# Sheet1.net
KiCad netlist of a schematic drawn in Altium Designer
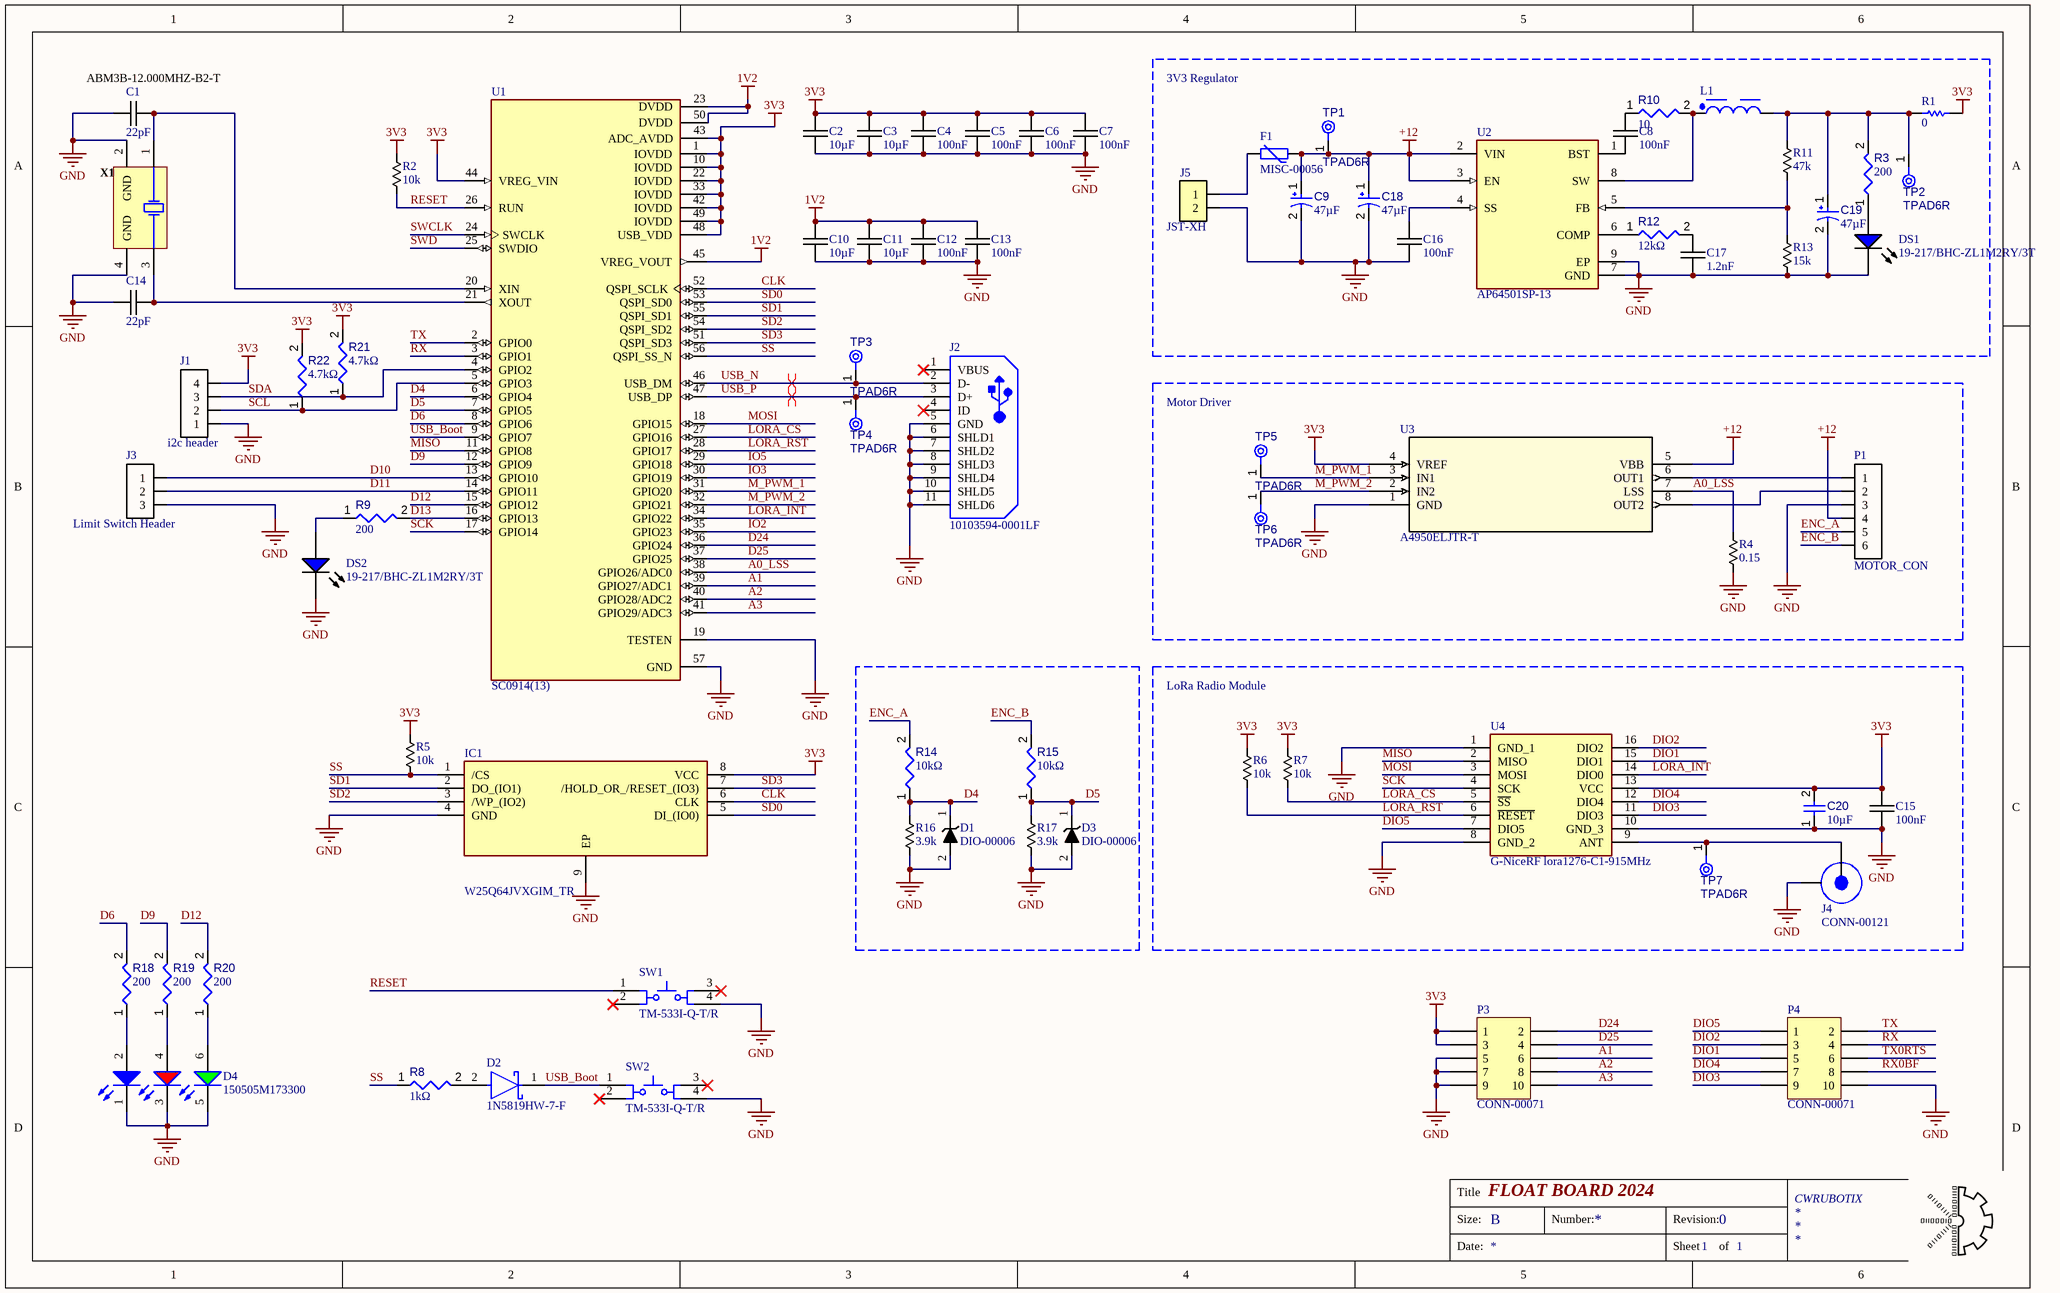
[diagram p0: Sheet1.SchDoc]

(export (version "E")
  (design (tool "Eeschema 10.0.6"))
  (components
    (comp (ref "C1")
      (value "22pF")
      (footprint "chip_0603")
      (description "CAP, 22pF, ±2%, 50V, C0G, 0603")
      (fields (field (name "MANUFACTURER") "Murata") (field (name "TOLERANCE") "2%"))
      (libsource (lib "Case Western Reserve University - Robotics Team") (part "cap_single_np"))
    )
    (comp (ref "C2")
      (value "10µF")
      (footprint "chip_0805")
      (description "CAP, 10uF, 10%, 6.3V, X7R, 0805")
      (fields (field (name "PART NUMBER") "CAP-00135") (field (name "MANUFACTURER") "Murata"))
      (libsource (lib "Case Western Reserve University - Robotics Team") (part "cap_single_np"))
    )
    (comp (ref "C3")
      (value "10µF")
      (footprint "chip_0805")
      (description "CAP, 10uF, 10%, 6.3V, X7R, 0805")
      (fields (field (name "PART NUMBER") "CAP-00135") (field (name "MANUFACTURER") "Murata"))
      (libsource (lib "Case Western Reserve University - Robotics Team") (part "cap_single_np"))
    )
    (comp (ref "C4")
      (value "100nF")
      (footprint "chip_0603")
      (description "CAP, 0.1uF, ±10%, 16V, X7R, 0603")
      (fields (field (name "TOLERANCE") "10%") (field (name "PART NUMBER") "CAP-00542"))
      (libsource (lib "Case Western Reserve University - Robotics Team") (part "cap_single_np"))
    )
    (comp (ref "C5")
      (value "100nF")
      (footprint "chip_0603")
      (description "CAP, 0.1uF, ±10%, 16V, X7R, 0603")
      (fields (field (name "TOLERANCE") "10%") (field (name "PART NUMBER") "CAP-00542"))
      (libsource (lib "Case Western Reserve University - Robotics Team") (part "cap_single_np"))
    )
    (comp (ref "C6")
      (value "100nF")
      (footprint "chip_0603")
      (description "CAP, 0.1uF, ±10%, 16V, X7R, 0603")
      (fields (field (name "TOLERANCE") "10%") (field (name "PART NUMBER") "CAP-00542"))
      (libsource (lib "Case Western Reserve University - Robotics Team") (part "cap_single_np"))
    )
    (comp (ref "C7")
      (value "100nF")
      (footprint "chip_0603")
      (description "CAP, 0.1uF, ±10%, 16V, X7R, 0603")
      (fields (field (name "TOLERANCE") "10%") (field (name "PART NUMBER") "CAP-00542"))
      (libsource (lib "Case Western Reserve University - Robotics Team") (part "cap_single_np"))
    )
    (comp (ref "C8")
      (value "100nF")
      (footprint "chip_0603")
      (description "CAP, 0.1uF, ±10%, 16V, X7R, 0603")
      (fields (field (name "TOLERANCE") "10%") (field (name "PART NUMBER") "CAP-00542"))
      (libsource (lib "Case Western Reserve University - Robotics Team") (part "cap_single_np"))
    )
    (comp (ref "C9")
      (value "47µF")
      (footprint "AVX-TAJ-C-2_L")
      (description "Standard Tantalum, 47 uF, +/- 10%, 16 V, -55 to 125 degC, 2312 (6032 Metric), RoHS, Tape and Reel")
      (fields (field (name "TOLERANCE") "10%") (field (name "MANUFACTURER") "AVX"))
      (libsource (lib "Case Western Reserve University - Robotics Team") (part "CAP-P-2"))
    )
    (comp (ref "C10")
      (value "10µF")
      (footprint "chip_0805")
      (description "CAP, 10uF, 10%, 6.3V, X7R, 0805")
      (fields (field (name "PART NUMBER") "CAP-00135") (field (name "MANUFACTURER") "Murata"))
      (libsource (lib "Case Western Reserve University - Robotics Team") (part "cap_single_np"))
    )
    (comp (ref "C11")
      (value "10µF")
      (footprint "chip_0805")
      (description "CAP, 10uF, 10%, 6.3V, X7R, 0805")
      (fields (field (name "PART NUMBER") "CAP-00135") (field (name "MANUFACTURER") "Murata"))
      (libsource (lib "Case Western Reserve University - Robotics Team") (part "cap_single_np"))
    )
    (comp (ref "C12")
      (value "100nF")
      (footprint "chip_0603")
      (description "CAP, 0.1uF, ±10%, 16V, X7R, 0603")
      (fields (field (name "TOLERANCE") "10%") (field (name "PART NUMBER") "CAP-00542"))
      (libsource (lib "Case Western Reserve University - Robotics Team") (part "cap_single_np"))
    )
    (comp (ref "C13")
      (value "100nF")
      (footprint "chip_0603")
      (description "CAP, 0.1uF, ±10%, 16V, X7R, 0603")
      (fields (field (name "TOLERANCE") "10%") (field (name "PART NUMBER") "CAP-00542"))
      (libsource (lib "Case Western Reserve University - Robotics Team") (part "cap_single_np"))
    )
    (comp (ref "C14")
      (value "22pF")
      (footprint "chip_0603")
      (description "CAP, 22pF, ±2%, 50V, C0G, 0603")
      (fields (field (name "MANUFACTURER") "Murata") (field (name "TOLERANCE") "2%"))
      (libsource (lib "Case Western Reserve University - Robotics Team") (part "cap_single_np"))
    )
    (comp (ref "C15")
      (value "100nF")
      (footprint "chip_0603")
      (description "CAP, 0.1uF, ±10%, 16V, X7R, 0603")
      (fields (field (name "TOLERANCE") "10%") (field (name "PART NUMBER") "CAP-00542"))
      (libsource (lib "Case Western Reserve University - Robotics Team") (part "cap_single_np"))
    )
    (comp (ref "C16")
      (value "100nF")
      (footprint "chip_0603")
      (description "CAP, 0.1uF, ±10%, 16V, X7R, 0603")
      (fields (field (name "TOLERANCE") "10%") (field (name "PART NUMBER") "CAP-00542"))
      (libsource (lib "Case Western Reserve University - Robotics Team") (part "cap_single_np"))
    )
    (comp (ref "C17")
      (value "1.2nF")
      (footprint "chip_0603")
      (description "CAP, 1200pF, ±1%, 50V, C0G, 0603")
      (fields (field (name "TOLERANCE") "1%") (field (name "PART NUMBER") "CAP-00470"))
      (libsource (lib "Case Western Reserve University - Robotics Team") (part "cap_single_np"))
    )
    (comp (ref "C18")
      (value "47µF")
      (footprint "AVX-TAJ-C-2_L")
      (description "Standard Tantalum, 47 uF, +/- 10%, 16 V, -55 to 125 degC, 2312 (6032 Metric), RoHS, Tape and Reel")
      (fields (field (name "TOLERANCE") "10%") (field (name "MANUFACTURER") "AVX"))
      (libsource (lib "Case Western Reserve University - Robotics Team") (part "CAP-P-2"))
    )
    (comp (ref "C19")
      (value "47µF")
      (footprint "AVX-TAJ-C-2_L")
      (description "Standard Tantalum, 47 uF, +/- 10%, 16 V, -55 to 125 degC, 2312 (6032 Metric), RoHS, Tape and Reel")
      (fields (field (name "TOLERANCE") "10%") (field (name "MANUFACTURER") "AVX"))
      (libsource (lib "Case Western Reserve University - Robotics Team") (part "CAP-P-2"))
    )
    (comp (ref "C20")
      (value "10µF")
      (footprint "CAPC0603(1608)100_L")
      (description "Chip Capacitor, 10µF +/-20%, 10V, 0603, Thickness 1 mm")
      (fields (field (name "TOLERANCE") "10%") (field (name "Comment") "Capacitor 10µF +/-20% 10V 0603"))
      (libsource (lib "Case Western Reserve University - Robotics Team") (part "CAP-NP-2"))
    )
    (comp (ref "D1")
      (value "DIO-00006")
      (footprint "sod323_0")
      (description "Dio Zen, 3.9V, 2%, 300mW, SOD-323")
      (fields (field (name "TOLERANCE") "2%") (field (name "MANUFACTURER") "ON Semi"))
      (libsource (lib "Case Western Reserve University - Robotics Team") (part "diode_1"))
    )
    (comp (ref "D2")
      (value "1N5819HW-7-F")
      (footprint "FP-SOD123-IPC_B")
      (description "Rectifier Diode, Schottky, 1 Phase, 1 Element, 1A, 40V V(RRM), Silicon")
      (libsource (lib "Case Western Reserve University - Robotics Team") (part "1d6ec82d83fb6aee721767c19dac4b9"))
    )
    (comp (ref "D3")
      (value "DIO-00006")
      (footprint "sod323_0")
      (description "Dio Zen, 3.9V, 2%, 300mW, SOD-323")
      (fields (field (name "TOLERANCE") "2%") (field (name "MANUFACTURER") "ON Semi"))
      (libsource (lib "Case Western Reserve University - Robotics Team") (part "diode_1"))
    )
    (comp (ref "D4")
      (value "150505M173300")
      (footprint "WL-SFTW_5050_150505M173300")
      (description "150505M173300 WL-SFTW SMT full-color TOP LED waterclear")
      (libsource (lib "Altium Content Vault") (part "WL-SFTW_150505M173300"))
    )
    (comp (ref "DS1")
      (value "19-217/BHC-ZL1M2RY/3T")
      (footprint "EVRL-0603-2_V")
      (description "Chip LED, Blue, 5 V, 25 mA, -40 to 85 degC, 2-Pin SMD (0603), RoHS, Tape and Reel")
      (fields (field (name "MANUFACTURER") "Everlight Electronics"))
      (libsource (lib "Case Western Reserve University - Robotics Team") (part "LED-BLUE-AK-2"))
    )
    (comp (ref "DS2")
      (value "19-217/BHC-ZL1M2RY/3T")
      (footprint "EVRL-0603-2_V")
      (description "Chip LED, Blue, 5 V, 25 mA, -40 to 85 degC, 2-Pin SMD (0603), RoHS, Tape and Reel")
      (fields (field (name "MANUFACTURER") "Everlight Electronics"))
      (libsource (lib "Case Western Reserve University - Robotics Team") (part "LED-BLUE-AK-2"))
    )
    (comp (ref "F1")
      (value "MISC-00056")
      (footprint "chip_1210")
      (description "PTC Fuse (Polyfuse), 16V 1.5A Hold, 3A Trip, 300ms")
      (fields (field (name "MANUFACTURER") "Littelfuse"))
      (libsource (lib "Case Western Reserve University - Robotics Team") (part "PTC_0"))
    )
    (comp (ref "IC1")
      (value "W25Q64JVXGIM_TR")
      (footprint "SamacSys:SON80P400X400X50-9N")
      (description "Integrated Circuit")
      (fields
        (field (name "MANUFACTURER_PART_NUMBER") "W25Q64JVXGIM TR")
        (field (name "MOUSER PART NUMBER") "454-W25Q64JVXGIMTR")
      )
      (libsource (lib "*") (part "W25Q64JVXGIM_TR"))
    )
    (comp (ref "J1")
      (value "i2c header")
      (footprint "JST_XH_4_0")
      (description "JST XH 4-Pos, 2.5mm Pitch, THT")
      (fields (field (name "PART NUMBER") "CONN-00116") (field (name "MANUFACTURER") "JST"))
      (libsource (lib "Case Western Reserve University - Robotics Team") (part "CONN-00118"))
    )
    (comp (ref "J2")
      (value "10103594-0001LF")
      (footprint "FCI-10103594-0001LF_V")
      (description "Micro USB 2.0 B Receptacle, 5 Position, Height 3.24 mm, -55 to 85 degC, RoHS, Tape and Reel")
      (fields (field (name "MANUFACTURER") "FCI Electronics"))
      (libsource (lib "Case Western Reserve University - Robotics Team") (part "USB-5-6SHLD"))
    )
    (comp (ref "J3")
      (value "Limit Switch Header")
      (footprint "JST_XH_3_0")
      (description "JST XH 3x1, TH")
      (fields (field (name "PART NUMBER") "CONN-00006") (field (name "MANUFACTURER") "JST"))
      (libsource (lib "Case Western Reserve University - Robotics Team") (part "CONN-00126"))
    )
    (comp (ref "J4")
      (value "CONN-00121")
      (footprint "SAMTEC_SMA-J-P-H-ST-EM1")
      (description "SMA Jack Female, 50 Ohm, Edge Launch, 20GHz")
      (fields (field (name "MANUFACTURER") "Samtec"))
      (libsource (lib "Case Western Reserve University - Robotics Team") (part "CONN-00121"))
    )
    (comp (ref "J5")
      (value "JST-XH")
      (footprint "HDDR_2x1_0")
      (description "Header, 2x1, 0.1\"")
      (fields (field (name "PART NUMBER") "CONN-00055") (field (name "MANUFACTURER") "Samtec"))
      (libsource (lib "Case Western Reserve University - Robotics Team") (part "CONN-00104"))
    )
    (comp (ref "L1")
      (value "7440430012")
      (footprint "WE-TPC_4828")
      (description "General Purpose Inductor, 1.2uH, 30%, 1 Element, Ferrite-Core, SMD, 1919")
      (fields (field (name "TOLERANCE") "30%"))
      (libsource (lib "Case Western Reserve University - Robotics Team") (part "Inductor - 2"))
    )
    (comp (ref "P1")
      (value "MOTOR_CON")
      (footprint "HDDR_6X1_0")
      (description "Header 6x1, 0.1\"")
      (fields (field (name "PART NUMBER") "CONN-00008"))
      (libsource (lib "Case Western Reserve University - Robotics Team") (part "CONN-00050"))
    )
    (comp (ref "P3")
      (value "CONN-00071")
      (footprint "SAMTEC_SMD_HDDR_5x2")
      (description "Header, 5x2, 0.1\", SMD")
      (fields (field (name "MANUFACTURER") "Samtec"))
      (libsource (lib "Case Western Reserve University - Robotics Team") (part "CONN-00071"))
    )
    (comp (ref "P4")
      (value "CONN-00071")
      (footprint "SAMTEC_SMD_HDDR_5x2")
      (description "Header, 5x2, 0.1\", SMD")
      (fields (field (name "MANUFACTURER") "Samtec"))
      (libsource (lib "Case Western Reserve University - Robotics Team") (part "CONN-00071"))
    )
    (comp (ref "R1")
      (value "0")
      (footprint "RESC1608X55X25ML10T15")
      (description "Chip Resistor, 0 Ohm, 0.1 W, -55 to 155 degC, 0603 (1608 Metric)")
      (fields (field (name "POWER") "100mW") (field (name "TOLERANCE") "5%"))
      (libsource (lib "") (part "RES-2_1"))
    )
    (comp (ref "R2")
      (value "10k")
      (footprint "chip_0603")
      (description "RES SMD 10K OHM 1% 1/4W 0603")
      (fields (field (name "TOLERANCE") "1%") (field (name "PART NUMBER") "RES-00306"))
      (libsource (lib "Case Western Reserve University - Robotics Team") (part "res_single"))
    )
    (comp (ref "R3")
      (value "200")
      (footprint "RESC0402(1005)_L")
      (description "Chip Resistor, 200 Ohms, +/-5 %, 63 mW, -55 to 155 degC, 0402")
      (fields (field (name "POWER") "63mW") (field (name "TOLERANCE") "5%"))
      (libsource (lib "Case Western Reserve University - Robotics Team") (part "RES-2"))
    )
    (comp (ref "R4")
      (value "0.15")
      (footprint "chip_0603")
      (description "RES, 0.15, 1%, 250mW, 0603")
      (fields (field (name "TOLERANCE") "1%") (field (name "PART NUMBER") "RES-00074"))
      (libsource (lib "Case Western Reserve University - Robotics Team") (part "res_single"))
    )
    (comp (ref "R5")
      (value "10k")
      (footprint "chip_0603")
      (description "RES SMD 10K OHM 1% 1/4W 0603")
      (fields (field (name "TOLERANCE") "1%") (field (name "PART NUMBER") "RES-00306"))
      (libsource (lib "Case Western Reserve University - Robotics Team") (part "res_single"))
    )
    (comp (ref "R6")
      (value "10k")
      (footprint "chip_0603")
      (description "RES SMD 10K OHM 1% 1/4W 0603")
      (fields (field (name "TOLERANCE") "1%") (field (name "PART NUMBER") "RES-00306"))
      (libsource (lib "Case Western Reserve University - Robotics Team") (part "res_single"))
    )
    (comp (ref "R7")
      (value "10k")
      (footprint "chip_0603")
      (description "RES SMD 10K OHM 1% 1/4W 0603")
      (fields (field (name "TOLERANCE") "1%") (field (name "PART NUMBER") "RES-00306"))
      (libsource (lib "Case Western Reserve University - Robotics Team") (part "res_single"))
    )
    (comp (ref "R8")
      (value "1kΩ")
      (footprint "RESC0402(1005)_L")
      (description "1K 0.063W 5% 0402 (1005 Metric)  SMD")
      (fields (field (name "POWER") "63mW") (field (name "TOLERANCE") "5%"))
      (libsource (lib "Case Western Reserve University - Robotics Team") (part "1KR2J"))
    )
    (comp (ref "R9")
      (value "200")
      (footprint "RESC0402(1005)_L")
      (description "Chip Resistor, 200 Ohms, +/-5 %, 63 mW, -55 to 155 degC, 0402")
      (fields (field (name "POWER") "63mW") (field (name "TOLERANCE") "5%"))
      (libsource (lib "Case Western Reserve University - Robotics Team") (part "RES-2"))
    )
    (comp (ref "R10")
      (value "10")
      (footprint "RESC0402(1005)_L")
      (description "Chip Resistor, 10 Ohms, +/-1 %, 63 mW, -55 to 155 degC, 0402")
      (fields (field (name "POWER") "63mW") (field (name "TOLERANCE") "1%"))
      (libsource (lib "Case Western Reserve University - Robotics Team") (part "RES-2"))
    )
    (comp (ref "R11")
      (value "47k")
      (footprint "chip_0603")
      (description "RES SMD 47K OHM 1% 1/10W 0603")
      (fields (field (name "PART NUMBER") "RES-00799") (field (name "MANUFACTURER") "Vishay Dale"))
      (libsource (lib "Case Western Reserve University - Robotics Team") (part "res_single"))
    )
    (comp (ref "R12")
      (value "12kΩ")
      (footprint "RESC0402(1005)_L")
      (description "12K 0.063W 1% 0402 (1005 Metric)  SMD")
      (fields (field (name "TOLERANCE") "1%") (field (name "POWER") "63mW"))
      (libsource (lib "Case Western Reserve University - Robotics Team") (part "12KR2F"))
    )
    (comp (ref "R13")
      (value "15k")
      (footprint "chip_0603")
      (description "RES SMD 15K OHM 1% 1/4W 0603")
      (fields (field (name "TOLERANCE") "1%") (field (name "PART NUMBER") "RES-00341"))
      (libsource (lib "Case Western Reserve University - Robotics Team") (part "res_single"))
    )
    (comp (ref "R14")
      (value "10kΩ")
      (footprint "RESC0402(1005)_L")
      (description "10K 0.063W 1% 0402 (1005 Metric)  SMD")
      (fields (field (name "POWER") "63mW") (field (name "TOLERANCE") "1%"))
      (libsource (lib "Case Western Reserve University - Robotics Team") (part "10KR2F"))
    )
    (comp (ref "R15")
      (value "10kΩ")
      (footprint "RESC0402(1005)_L")
      (description "10K 0.063W 1% 0402 (1005 Metric)  SMD")
      (fields (field (name "POWER") "63mW") (field (name "TOLERANCE") "1%"))
      (libsource (lib "Case Western Reserve University - Robotics Team") (part "10KR2F"))
    )
    (comp (ref "R16")
      (value "3.9k")
      (footprint "chip_0603")
      (description "RES SMD 3.9K OHM 1% 1/10W 0603")
      (fields (field (name "PART NUMBER") "RES-00782") (field (name "TOLERANCE") "1%"))
      (libsource (lib "Case Western Reserve University - Robotics Team") (part "res_single"))
    )
    (comp (ref "R17")
      (value "3.9k")
      (footprint "chip_0603")
      (description "RES SMD 3.9K OHM 1% 1/10W 0603")
      (fields (field (name "PART NUMBER") "RES-00782") (field (name "TOLERANCE") "1%"))
      (libsource (lib "Case Western Reserve University - Robotics Team") (part "res_single"))
    )
    (comp (ref "R18")
      (value "200")
      (footprint "RESC0402(1005)_L")
      (description "Chip Resistor, 200 Ohms, +/-5 %, 63 mW, -55 to 155 degC, 0402")
      (fields (field (name "POWER") "63mW") (field (name "TOLERANCE") "5%"))
      (libsource (lib "Case Western Reserve University - Robotics Team") (part "RES-2"))
    )
    (comp (ref "R19")
      (value "200")
      (footprint "RESC0402(1005)_L")
      (description "Chip Resistor, 200 Ohms, +/-5 %, 63 mW, -55 to 155 degC, 0402")
      (fields (field (name "POWER") "63mW") (field (name "TOLERANCE") "5%"))
      (libsource (lib "Case Western Reserve University - Robotics Team") (part "RES-2"))
    )
    (comp (ref "R20")
      (value "200")
      (footprint "RESC0402(1005)_L")
      (description "Chip Resistor, 200 Ohms, +/-5 %, 63 mW, -55 to 155 degC, 0402")
      (fields (field (name "POWER") "63mW") (field (name "TOLERANCE") "5%"))
      (libsource (lib "Case Western Reserve University - Robotics Team") (part "RES-2"))
    )
    (comp (ref "R21")
      (value "4.7kΩ")
      (footprint "RESC0402(1005)_L")
      (description "4K7 0.063W 1% 0402 (1005 Metric)  SMD")
      (fields (field (name "POWER") "63mW") (field (name "TOLERANCE") "1%"))
      (libsource (lib "Case Western Reserve University - Robotics Team") (part "4D7KR2F"))
    )
    (comp (ref "R22")
      (value "4.7kΩ")
      (footprint "RESC0402(1005)_L")
      (description "4K7 0.063W 1% 0402 (1005 Metric)  SMD")
      (fields (field (name "POWER") "63mW") (field (name "TOLERANCE") "1%"))
      (libsource (lib "Case Western Reserve University - Robotics Team") (part "4D7KR2F"))
    )
    (comp (ref "SW1")
      (value "TM-533I-Q-T/R")
      (footprint "MULT-TM-533I-Q_V")
      (description "Tactile Switch, SPNO, -25 to 70 degC, 4-Pin SMD, RoHS, Tape and Reel")
      (fields (field (name "MANUFACTURER") "Multicomp"))
      (libsource (lib "Case Western Reserve University - Robotics Team") (part "SW-SPST-NO-4"))
    )
    (comp (ref "SW2")
      (value "TM-533I-Q-T/R")
      (footprint "MULT-TM-533I-Q_V")
      (description "Tactile Switch, SPNO, -25 to 70 degC, 4-Pin SMD, RoHS, Tape and Reel")
      (fields (field (name "MANUFACTURER") "Multicomp"))
      (libsource (lib "Case Western Reserve University - Robotics Team") (part "SW-SPST-NO-4"))
    )
    (comp (ref "TP1")
      (value "TPAD6R")
      (footprint "TP06R")
      (description "0.6mm round")
      (libsource (lib "Case Western Reserve University - Robotics Team") (part "CMP-001-0001-4"))
    )
    (comp (ref "TP2")
      (value "TPAD6R")
      (footprint "TP06R")
      (description "0.6mm round")
      (libsource (lib "Case Western Reserve University - Robotics Team") (part "CMP-001-0001-4"))
    )
    (comp (ref "TP3")
      (value "TPAD6R")
      (footprint "TP06R")
      (description "0.6mm round")
      (libsource (lib "Case Western Reserve University - Robotics Team") (part "CMP-001-0001-4"))
    )
    (comp (ref "TP4")
      (value "TPAD6R")
      (footprint "TP06R")
      (description "0.6mm round")
      (libsource (lib "Case Western Reserve University - Robotics Team") (part "CMP-001-0001-4"))
    )
    (comp (ref "TP5")
      (value "TPAD6R")
      (footprint "TP06R")
      (description "0.6mm round")
      (libsource (lib "Case Western Reserve University - Robotics Team") (part "CMP-001-0001-4"))
    )
    (comp (ref "TP6")
      (value "TPAD6R")
      (footprint "TP06R")
      (description "0.6mm round")
      (libsource (lib "Case Western Reserve University - Robotics Team") (part "CMP-001-0001-4"))
    )
    (comp (ref "TP7")
      (value "TPAD6R")
      (footprint "TP06R")
      (description "0.6mm round")
      (libsource (lib "Case Western Reserve University - Robotics Team") (part "CMP-001-0001-4"))
    )
    (comp (ref "U1")
      (value "SC0914(13)")
      (footprint "QFN40P700X700X90-57N")
      (description "ARMÂ® CortexÂ®-M0+ - Microcontroller IC 32-Bit Dual-Core 133MHz External Program Memory 56-QFN (7x7)")
      (fields (field (name "MF") "Raspberry Pi"))
      (libsource (lib "Case Western Reserve University - Robotics Team") (part "SC0914(13)"))
    )
    (comp (ref "U2")
      (value "AP64501SP-13")
      (footprint "FP-SO-8EP-IPC_B")
      (description "Switching Regulator, Current-mode, 630kHz Switching Freq-Max, PDSO8")
      (libsource (lib "Case Western Reserve University - Robotics Team") (part "5ebf8146ffb11b38024cfc6b6736e1a"))
    )
    (comp (ref "U3")
      (value "A4950ELJTR-T")
      (footprint "DDA0008H_L")
      (description "No Description Available")
      (libsource (lib "Case Western Reserve University - Robotics Team") (part "A4950ELJTR-T"))
    )
    (comp (ref "U4")
      (value "G-NiceRF lora1276-C1-915MHz")
      (footprint "New footprint 1")
      (description "Lora Radio")
      (libsource (lib "Case Western Reserve University - Robotics Team") (part "New symbol 1"))
    )
    (comp (ref "X1")
      (value "ABM3B-12.000MHZ-B2-T")
      (footprint "ABRA-ABM3B-4_V")
      (description "Ceramic SMD Crystal, 12 MHz, +/- 20 ppm, 18 pF, -20 to 70 degC, 4-Pin SMD, RoHS, Tape and Reel")
      (fields (field (name "TOLERANCE") "20ppm") (field (name "MANUFACTURER") "Abracon"))
      (libsource (lib "Case Western Reserve University - Robotics Team") (part "XTAL-1-3-4"))
    )
  )
  (nets
    (net (code "1") (name "+12") (class "Default")
      (node (ref "C18") (pin "1") (pinfunction "1_1") (pintype "passive"))
      (node (ref "C9") (pin "1") (pinfunction "1_1") (pintype "passive"))
      (node (ref "F1") (pin "1") (pinfunction "1_1") (pintype "passive"))
      (node (ref "P1") (pin "4") (pinfunction "4_4") (pintype "passive"))
      (node (ref "TP1") (pin "1") (pinfunction "TP_1") (pintype "passive"))
      (node (ref "U2") (pin "2") (pinfunction "VIN_2") (pintype "power_in"))
      (node (ref "U2") (pin "3") (pinfunction "EN_3") (pintype "input"))
      (node (ref "U3") (pin "5") (pinfunction "VBB_5") (pintype "power_in"))
    )
    (net (code "2") (name "/A0_LSS") (class "Default")
      (node (ref "R4") (pin "1") (pinfunction "1_1") (pintype "passive"))
      (node (ref "U1") (pin "38") (pinfunction "GPIO26/ADC0_38") (pintype "bidirectional"))
      (node (ref "U3") (pin "7") (pinfunction "LSS_7") (pintype "passive"))
    )
    (net (code "3") (name "/A1") (class "Default")
      (node (ref "P3") (pin "6") (pinfunction "6_6") (pintype "passive"))
      (node (ref "U1") (pin "39") (pinfunction "GPIO27/ADC1_39") (pintype "bidirectional"))
    )
    (net (code "4") (name "/A2") (class "Default")
      (node (ref "P3") (pin "8") (pinfunction "8_8") (pintype "passive"))
      (node (ref "U1") (pin "40") (pinfunction "GPIO28/ADC2_40") (pintype "bidirectional"))
    )
    (net (code "5") (name "/A3") (class "Default")
      (node (ref "P3") (pin "10") (pinfunction "10_10") (pintype "passive"))
      (node (ref "U1") (pin "41") (pinfunction "GPIO29/ADC3_41") (pintype "bidirectional"))
    )
    (net (code "6") (name "/CLK") (class "Default")
      (node (ref "IC1") (pin "6") (pinfunction "CLK_6") (pintype "passive"))
      (node (ref "U1") (pin "52") (pinfunction "QSPI_SCLK_52") (pintype "bidirectional"))
    )
    (net (code "7") (name "/D4") (class "Default")
      (node (ref "D1") (pin "1") (pinfunction "1_1") (pintype "passive"))
      (node (ref "R14") (pin "1") (pinfunction "1_1") (pintype "passive"))
      (node (ref "R16") (pin "1") (pinfunction "1_1") (pintype "passive"))
      (node (ref "U1") (pin "6") (pinfunction "GPIO4_6") (pintype "bidirectional"))
    )
    (net (code "8") (name "/D5") (class "Default")
      (node (ref "D3") (pin "1") (pinfunction "1_1") (pintype "passive"))
      (node (ref "R15") (pin "1") (pinfunction "1_1") (pintype "passive"))
      (node (ref "R17") (pin "1") (pinfunction "1_1") (pintype "passive"))
      (node (ref "U1") (pin "7") (pinfunction "GPIO5_7") (pintype "bidirectional"))
    )
    (net (code "9") (name "/D6") (class "Default")
      (node (ref "R18") (pin "2") (pinfunction "2_2") (pintype "passive"))
      (node (ref "U1") (pin "8") (pinfunction "GPIO6_8") (pintype "bidirectional"))
    )
    (net (code "10") (name "/D9") (class "Default")
      (node (ref "R19") (pin "2") (pinfunction "2_2") (pintype "passive"))
      (node (ref "U1") (pin "12") (pinfunction "GPIO9_12") (pintype "bidirectional"))
    )
    (net (code "11") (name "/D10") (class "Default")
      (node (ref "J3") (pin "1") (pinfunction "1_1") (pintype "passive"))
      (node (ref "U1") (pin "13") (pinfunction "GPIO10_13") (pintype "bidirectional"))
    )
    (net (code "12") (name "/D11") (class "Default")
      (node (ref "J3") (pin "2") (pinfunction "2_2") (pintype "passive"))
      (node (ref "U1") (pin "14") (pinfunction "GPIO11_14") (pintype "bidirectional"))
    )
    (net (code "13") (name "/D12") (class "Default")
      (node (ref "R20") (pin "2") (pinfunction "2_2") (pintype "passive"))
      (node (ref "U1") (pin "15") (pinfunction "GPIO12_15") (pintype "bidirectional"))
    )
    (net (code "14") (name "/D13") (class "Default")
      (node (ref "R9") (pin "2") (pinfunction "2_2") (pintype "passive"))
      (node (ref "U1") (pin "16") (pinfunction "GPIO13_16") (pintype "bidirectional"))
    )
    (net (code "15") (name "/D24") (class "Default")
      (node (ref "P3") (pin "2") (pinfunction "2_2") (pintype "passive"))
      (node (ref "U1") (pin "36") (pinfunction "GPIO24_36") (pintype "bidirectional"))
    )
    (net (code "16") (name "/D25") (class "Default")
      (node (ref "P3") (pin "4") (pinfunction "4_4") (pintype "passive"))
      (node (ref "U1") (pin "37") (pinfunction "GPIO25_37") (pintype "bidirectional"))
    )
    (net (code "17") (name "/DIO1") (class "Default")
      (node (ref "P4") (pin "5") (pinfunction "5_5") (pintype "passive"))
      (node (ref "U4") (pin "15") (pinfunction "DIO1_15") (pintype "passive"))
    )
    (net (code "18") (name "/DIO2") (class "Default")
      (node (ref "P4") (pin "3") (pinfunction "3_3") (pintype "passive"))
      (node (ref "U4") (pin "16") (pinfunction "DIO2_16") (pintype "passive"))
    )
    (net (code "19") (name "/DIO3") (class "Default")
      (node (ref "P4") (pin "9") (pinfunction "9_9") (pintype "passive"))
      (node (ref "U4") (pin "11") (pinfunction "DIO3_11") (pintype "passive"))
    )
    (net (code "20") (name "/DIO4") (class "Default")
      (node (ref "P4") (pin "7") (pinfunction "7_7") (pintype "passive"))
      (node (ref "U4") (pin "12") (pinfunction "DIO4_12") (pintype "passive"))
    )
    (net (code "21") (name "/DIO5") (class "Default")
      (node (ref "P4") (pin "1") (pinfunction "1_1") (pintype "passive"))
      (node (ref "U4") (pin "7") (pinfunction "DIO5_7") (pintype "passive"))
    )
    (net (code "22") (name "/ENC_A") (class "Default")
      (node (ref "P1") (pin "5") (pinfunction "5_5") (pintype "passive"))
      (node (ref "R14") (pin "2") (pinfunction "2_2") (pintype "passive"))
    )
    (net (code "23") (name "/ENC_B") (class "Default")
      (node (ref "P1") (pin "6") (pinfunction "6_6") (pintype "passive"))
      (node (ref "R15") (pin "2") (pinfunction "2_2") (pintype "passive"))
    )
    (net (code "24") (name "/IO2") (class "Default")
      (node (ref "U1") (pin "35") (pinfunction "GPIO23_35") (pintype "bidirectional"))
    )
    (net (code "25") (name "/IO3") (class "Default")
      (node (ref "U1") (pin "30") (pinfunction "GPIO19_30") (pintype "bidirectional"))
    )
    (net (code "26") (name "/IO5") (class "Default")
      (node (ref "U1") (pin "29") (pinfunction "GPIO18_29") (pintype "bidirectional"))
    )
    (net (code "27") (name "/LORA_CS") (class "Default")
      (node (ref "R7") (pin "2") (pinfunction "2_2") (pintype "passive"))
      (node (ref "U1") (pin "27") (pinfunction "GPIO16_27") (pintype "bidirectional"))
      (node (ref "U4") (pin "5") (pinfunction "~{SS}_5") (pintype "passive"))
    )
    (net (code "28") (name "/LORA_INT") (class "Default")
      (node (ref "U1") (pin "34") (pinfunction "GPIO22_34") (pintype "bidirectional"))
      (node (ref "U4") (pin "14") (pinfunction "DIO0_14") (pintype "passive"))
    )
    (net (code "29") (name "/LORA_RST") (class "Default")
      (node (ref "R6") (pin "2") (pinfunction "2_2") (pintype "passive"))
      (node (ref "U1") (pin "28") (pinfunction "GPIO17_28") (pintype "bidirectional"))
      (node (ref "U4") (pin "6") (pinfunction "~{RESET}_6") (pintype "passive"))
    )
    (net (code "30") (name "/MISO") (class "Default")
      (node (ref "U1") (pin "11") (pinfunction "GPIO8_11") (pintype "bidirectional"))
      (node (ref "U4") (pin "2") (pinfunction "MISO_2") (pintype "passive"))
    )
    (net (code "31") (name "/MOSI") (class "Default")
      (node (ref "U1") (pin "18") (pinfunction "GPIO15_18") (pintype "bidirectional"))
      (node (ref "U4") (pin "3") (pinfunction "MOSI_3") (pintype "passive"))
    )
    (net (code "32") (name "/M_PWM_1") (class "Default")
      (node (ref "TP5") (pin "1") (pinfunction "TP_1") (pintype "passive"))
      (node (ref "U1") (pin "31") (pinfunction "GPIO20_31") (pintype "bidirectional"))
      (node (ref "U3") (pin "3") (pinfunction "IN1_3") (pintype "input"))
    )
    (net (code "33") (name "/M_PWM_2") (class "Default")
      (node (ref "TP6") (pin "1") (pinfunction "TP_1") (pintype "passive"))
      (node (ref "U1") (pin "32") (pinfunction "GPIO21_32") (pintype "bidirectional"))
      (node (ref "U3") (pin "2") (pinfunction "IN2_2") (pintype "input"))
    )
    (net (code "34") (name "/RESET") (class "Default")
      (node (ref "R2") (pin "2") (pinfunction "2_2") (pintype "passive"))
      (node (ref "SW1") (pin "1") (pinfunction "1_1") (pintype "passive"))
      (node (ref "U1") (pin "26") (pinfunction "RUN_26") (pintype "input"))
    )
    (net (code "35") (name "/RX") (class "Default")
      (node (ref "P4") (pin "4") (pinfunction "4_4") (pintype "passive"))
      (node (ref "U1") (pin "3") (pinfunction "GPIO1_3") (pintype "bidirectional"))
    )
    (net (code "36") (name "/RX0BF") (class "Default")
      (node (ref "P4") (pin "8") (pinfunction "8_8") (pintype "passive"))
    )
    (net (code "37") (name "/SCK") (class "Default")
      (node (ref "U1") (pin "17") (pinfunction "GPIO14_17") (pintype "bidirectional"))
      (node (ref "U4") (pin "4") (pinfunction "SCK_4") (pintype "passive"))
    )
    (net (code "38") (name "/SCL") (class "Default")
      (node (ref "J1") (pin "2") (pinfunction "2_2") (pintype "passive"))
      (node (ref "R22") (pin "1") (pinfunction "1_1") (pintype "passive"))
      (node (ref "U1") (pin "5") (pinfunction "GPIO3_5") (pintype "bidirectional"))
    )
    (net (code "39") (name "/SD0") (class "Default")
      (node (ref "IC1") (pin "5") (pinfunction "DI_(IO0)_5") (pintype "passive"))
      (node (ref "U1") (pin "53") (pinfunction "QSPI_SD0_53") (pintype "bidirectional"))
    )
    (net (code "40") (name "/SD1") (class "Default")
      (node (ref "IC1") (pin "2") (pinfunction "DO_(IO1)_2") (pintype "passive"))
      (node (ref "U1") (pin "55") (pinfunction "QSPI_SD1_55") (pintype "bidirectional"))
    )
    (net (code "41") (name "/SD2") (class "Default")
      (node (ref "IC1") (pin "3") (pinfunction "/WP_(IO2)_3") (pintype "passive"))
      (node (ref "U1") (pin "54") (pinfunction "QSPI_SD2_54") (pintype "bidirectional"))
    )
    (net (code "42") (name "/SD3") (class "Default")
      (node (ref "IC1") (pin "7") (pinfunction "/HOLD_OR_/RESET_(IO3)_7") (pintype "passive"))
      (node (ref "U1") (pin "51") (pinfunction "QSPI_SD3_51") (pintype "bidirectional"))
    )
    (net (code "43") (name "/SDA") (class "Default")
      (node (ref "J1") (pin "3") (pinfunction "3_3") (pintype "passive"))
      (node (ref "R21") (pin "1") (pinfunction "1_1") (pintype "passive"))
      (node (ref "U1") (pin "4") (pinfunction "GPIO2_4") (pintype "bidirectional"))
    )
    (net (code "44") (name "/SS") (class "Default")
      (node (ref "IC1") (pin "1") (pinfunction "/CS_1") (pintype "passive"))
      (node (ref "R5") (pin "2") (pinfunction "2_2") (pintype "passive"))
      (node (ref "R8") (pin "1") (pinfunction "1_1") (pintype "passive"))
      (node (ref "U1") (pin "56") (pinfunction "QSPI_SS_N_56") (pintype "bidirectional"))
    )
    (net (code "45") (name "/SWCLK") (class "Default")
      (node (ref "U1") (pin "24") (pinfunction "SWCLK_24") (pintype "input"))
    )
    (net (code "46") (name "/SWD") (class "Default")
      (node (ref "U1") (pin "25") (pinfunction "SWDIO_25") (pintype "bidirectional"))
    )
    (net (code "47") (name "/TX") (class "Default")
      (node (ref "P4") (pin "2") (pinfunction "2_2") (pintype "passive"))
      (node (ref "U1") (pin "2") (pinfunction "GPIO0_2") (pintype "bidirectional"))
    )
    (net (code "48") (name "/TX0RTS") (class "Default")
      (node (ref "P4") (pin "6") (pinfunction "6_6") (pintype "passive"))
    )
    (net (code "49") (name "/USB_Boot") (class "Default")
      (node (ref "D2") (pin "1") (pinfunction "C_1") (pintype "passive"))
      (node (ref "SW2") (pin "1") (pinfunction "1_1") (pintype "passive"))
      (node (ref "U1") (pin "9") (pinfunction "GPIO7_9") (pintype "bidirectional"))
    )
    (net (code "50") (name "/USB_N") (class "Default")
      (node (ref "J2") (pin "2") (pinfunction "D-_2") (pintype "passive"))
      (node (ref "TP3") (pin "1") (pinfunction "TP_1") (pintype "passive"))
      (node (ref "U1") (pin "46") (pinfunction "USB_DM_46") (pintype "bidirectional"))
    )
    (net (code "51") (name "/USB_P") (class "Default")
      (node (ref "J2") (pin "3") (pinfunction "D+_3") (pintype "passive"))
      (node (ref "TP4") (pin "1") (pinfunction "TP_1") (pintype "passive"))
      (node (ref "U1") (pin "47") (pinfunction "USB_DP_47") (pintype "bidirectional"))
    )
    (net (code "52") (name "1V2") (class "Default")
      (node (ref "C10") (pin "1") (pinfunction "1_1") (pintype "passive"))
      (node (ref "C11") (pin "1") (pinfunction "1_1") (pintype "passive"))
      (node (ref "C12") (pin "1") (pinfunction "1_1") (pintype "passive"))
      (node (ref "C13") (pin "1") (pinfunction "1_1") (pintype "passive"))
      (node (ref "U1") (pin "23") (pinfunction "DVDD_23") (pintype "power_in"))
      (node (ref "U1") (pin "45") (pinfunction "VREG_VOUT_45") (pintype "output"))
      (node (ref "U1") (pin "50") (pinfunction "DVDD_50") (pintype "power_in"))
    )
    (net (code "53") (name "3V3") (class "Default")
      (node (ref "C15") (pin "1") (pinfunction "1_1") (pintype "passive"))
      (node (ref "C2") (pin "1") (pinfunction "1_1") (pintype "passive"))
      (node (ref "C20") (pin "2") (pinfunction "2_2") (pintype "passive"))
      (node (ref "C3") (pin "1") (pinfunction "1_1") (pintype "passive"))
      (node (ref "C4") (pin "1") (pinfunction "1_1") (pintype "passive"))
      (node (ref "C5") (pin "1") (pinfunction "1_1") (pintype "passive"))
      (node (ref "C6") (pin "1") (pinfunction "1_1") (pintype "passive"))
      (node (ref "C7") (pin "1") (pinfunction "1_1") (pintype "passive"))
      (node (ref "IC1") (pin "8") (pinfunction "VCC_8") (pintype "passive"))
      (node (ref "J1") (pin "4") (pinfunction "4_4") (pintype "passive"))
      (node (ref "P3") (pin "1") (pinfunction "1_1") (pintype "passive"))
      (node (ref "P3") (pin "3") (pinfunction "3_3") (pintype "passive"))
      (node (ref "R1") (pin "2") (pinfunction "2_2") (pintype "passive"))
      (node (ref "R2") (pin "1") (pinfunction "1_1") (pintype "passive"))
      (node (ref "R21") (pin "2") (pinfunction "2_2") (pintype "passive"))
      (node (ref "R22") (pin "2") (pinfunction "2_2") (pintype "passive"))
      (node (ref "R5") (pin "1") (pinfunction "1_1") (pintype "passive"))
      (node (ref "R6") (pin "1") (pinfunction "1_1") (pintype "passive"))
      (node (ref "R7") (pin "1") (pinfunction "1_1") (pintype "passive"))
      (node (ref "U1") (pin "1") (pinfunction "IOVDD_1") (pintype "power_in"))
      (node (ref "U1") (pin "10") (pinfunction "IOVDD_10") (pintype "power_in"))
      (node (ref "U1") (pin "22") (pinfunction "IOVDD_22") (pintype "power_in"))
      (node (ref "U1") (pin "33") (pinfunction "IOVDD_33") (pintype "power_in"))
      (node (ref "U1") (pin "42") (pinfunction "IOVDD_42") (pintype "power_in"))
      (node (ref "U1") (pin "43") (pinfunction "ADC_AVDD_43") (pintype "power_in"))
      (node (ref "U1") (pin "44") (pinfunction "VREG_VIN_44") (pintype "input"))
      (node (ref "U1") (pin "48") (pinfunction "USB_VDD_48") (pintype "power_in"))
      (node (ref "U1") (pin "49") (pinfunction "IOVDD_49") (pintype "power_in"))
      (node (ref "U3") (pin "4") (pinfunction "VREF_4") (pintype "input"))
      (node (ref "U4") (pin "13") (pinfunction "VCC_13") (pintype "passive"))
    )
    (net (code "54") (name "GND") (class "Default")
      (node (ref "C1") (pin "2") (pinfunction "2_2") (pintype "passive"))
      (node (ref "C10") (pin "2") (pinfunction "2_2") (pintype "passive"))
      (node (ref "C11") (pin "2") (pinfunction "2_2") (pintype "passive"))
      (node (ref "C12") (pin "2") (pinfunction "2_2") (pintype "passive"))
      (node (ref "C13") (pin "2") (pinfunction "2_2") (pintype "passive"))
      (node (ref "C14") (pin "1") (pinfunction "1_1") (pintype "passive"))
      (node (ref "C15") (pin "2") (pinfunction "2_2") (pintype "passive"))
      (node (ref "C16") (pin "2") (pinfunction "2_2") (pintype "passive"))
      (node (ref "C17") (pin "2") (pinfunction "2_2") (pintype "passive"))
      (node (ref "C18") (pin "2") (pinfunction "2_2") (pintype "passive"))
      (node (ref "C19") (pin "2") (pinfunction "2_2") (pintype "passive"))
      (node (ref "C2") (pin "2") (pinfunction "2_2") (pintype "passive"))
      (node (ref "C20") (pin "1") (pinfunction "1_1") (pintype "passive"))
      (node (ref "C3") (pin "2") (pinfunction "2_2") (pintype "passive"))
      (node (ref "C4") (pin "2") (pinfunction "2_2") (pintype "passive"))
      (node (ref "C5") (pin "2") (pinfunction "2_2") (pintype "passive"))
      (node (ref "C6") (pin "2") (pinfunction "2_2") (pintype "passive"))
      (node (ref "C7") (pin "2") (pinfunction "2_2") (pintype "passive"))
      (node (ref "C9") (pin "2") (pinfunction "2_2") (pintype "passive"))
      (node (ref "D1") (pin "2") (pinfunction "2_2") (pintype "passive"))
      (node (ref "D3") (pin "2") (pinfunction "2_2") (pintype "passive"))
      (node (ref "D4") (pin "1") (pinfunction "K_1") (pintype "passive"))
      (node (ref "D4") (pin "3") (pinfunction "K_3") (pintype "passive"))
      (node (ref "D4") (pin "5") (pinfunction "K_5") (pintype "passive"))
      (node (ref "DS1") (pin "2") (pinfunction "K_2") (pintype "passive"))
      (node (ref "DS2") (pin "2") (pinfunction "K_2") (pintype "passive"))
      (node (ref "IC1") (pin "4") (pinfunction "GND_4") (pintype "passive"))
      (node (ref "IC1") (pin "9") (pinfunction "EP_9") (pintype "passive"))
      (node (ref "J1") (pin "1") (pinfunction "1_1") (pintype "passive"))
      (node (ref "J2") (pin "10") (pinfunction "SHLD5_10") (pintype "passive"))
      (node (ref "J2") (pin "11") (pinfunction "SHLD6_11") (pintype "passive"))
      (node (ref "J2") (pin "5") (pinfunction "GND_5") (pintype "passive"))
      (node (ref "J2") (pin "6") (pinfunction "SHLD1_6") (pintype "passive"))
      (node (ref "J2") (pin "7") (pinfunction "SHLD2_7") (pintype "passive"))
      (node (ref "J2") (pin "8") (pinfunction "SHLD3_8") (pintype "passive"))
      (node (ref "J2") (pin "9") (pinfunction "SHLD4_9") (pintype "passive"))
      (node (ref "J3") (pin "3") (pinfunction "3_3") (pintype "passive"))
      (node (ref "J4") (pin "2") (pinfunction "2_2") (pintype "passive"))
      (node (ref "J5") (pin "2") (pinfunction "2_2") (pintype "passive"))
      (node (ref "P1") (pin "3") (pinfunction "3_3") (pintype "passive"))
      (node (ref "P3") (pin "5") (pinfunction "5_5") (pintype "passive"))
      (node (ref "P3") (pin "7") (pinfunction "7_7") (pintype "passive"))
      (node (ref "P3") (pin "9") (pinfunction "9_9") (pintype "passive"))
      (node (ref "P4") (pin "10") (pinfunction "10_10") (pintype "passive"))
      (node (ref "R13") (pin "2") (pinfunction "2_2") (pintype "passive"))
      (node (ref "R16") (pin "2") (pinfunction "2_2") (pintype "passive"))
      (node (ref "R17") (pin "2") (pinfunction "2_2") (pintype "passive"))
      (node (ref "R4") (pin "2") (pinfunction "2_2") (pintype "passive"))
      (node (ref "SW1") (pin "4") (pinfunction "4_4") (pintype "passive"))
      (node (ref "SW2") (pin "4") (pinfunction "4_4") (pintype "passive"))
      (node (ref "U1") (pin "19") (pinfunction "TESTEN_19") (pintype "passive"))
      (node (ref "U1") (pin "57") (pinfunction "GND_57") (pintype "power_in"))
      (node (ref "U2") (pin "7") (pinfunction "GND_7") (pintype "power_in"))
      (node (ref "U2") (pin "9") (pinfunction "EP_9") (pintype "passive"))
      (node (ref "U3") (pin "1") (pinfunction "GND_1") (pintype "power_in"))
      (node (ref "U4") (pin "1") (pinfunction "GND_1_1") (pintype "passive"))
      (node (ref "U4") (pin "10") (pinfunction "GND_3_10") (pintype "passive"))
      (node (ref "U4") (pin "8") (pinfunction "GND_2_8") (pintype "passive"))
      (node (ref "X1") (pin "2") (pinfunction "GND_2") (pintype "power_in"))
      (node (ref "X1") (pin "4") (pinfunction "GND_4") (pintype "power_in"))
    )
    (net (code "55") (name "Net-(C8-Pad1)") (class "Default")
      (node (ref "C8") (pin "1") (pinfunction "1_1") (pintype "passive"))
      (node (ref "R10") (pin "1") (pinfunction "1_1") (pintype "passive"))
    )
    (net (code "56") (name "Net-(C17-Pad1)") (class "Default")
      (node (ref "C17") (pin "1") (pinfunction "1_1") (pintype "passive"))
      (node (ref "R12") (pin "2") (pinfunction "2_2") (pintype "passive"))
    )
    (net (code "57") (name "Net-(D2-A)") (class "Default")
      (node (ref "D2") (pin "2") (pinfunction "A_2") (pintype "passive"))
      (node (ref "R8") (pin "2") (pinfunction "2_2") (pintype "passive"))
    )
    (net (code "58") (name "Net-(D4-A-Pad2)") (class "Default")
      (node (ref "D4") (pin "2") (pinfunction "A_2") (pintype "passive"))
      (node (ref "R18") (pin "1") (pinfunction "1_1") (pintype "passive"))
    )
    (net (code "59") (name "Net-(D4-A-Pad4)") (class "Default")
      (node (ref "D4") (pin "4") (pinfunction "A_4") (pintype "passive"))
      (node (ref "R19") (pin "1") (pinfunction "1_1") (pintype "passive"))
    )
    (net (code "60") (name "Net-(D4-A-Pad6)") (class "Default")
      (node (ref "D4") (pin "6") (pinfunction "A_6") (pintype "passive"))
      (node (ref "R20") (pin "1") (pinfunction "1_1") (pintype "passive"))
    )
    (net (code "61") (name "Net-(DS1-A)") (class "Default")
      (node (ref "DS1") (pin "1") (pinfunction "A_1") (pintype "passive"))
      (node (ref "R3") (pin "1") (pinfunction "1_1") (pintype "passive"))
    )
    (net (code "62") (name "Net-(DS2-A)") (class "Default")
      (node (ref "DS2") (pin "1") (pinfunction "A_1") (pintype "passive"))
      (node (ref "R9") (pin "1") (pinfunction "1_1") (pintype "passive"))
    )
    (net (code "63") (name "Net-(F1-Pad2)") (class "Default")
      (node (ref "F1") (pin "2") (pinfunction "2_2") (pintype "passive"))
      (node (ref "J5") (pin "1") (pinfunction "1_1") (pintype "passive"))
    )
    (net (code "64") (name "Net-(TP2-TP)") (class "Default")
      (node (ref "C19") (pin "1") (pinfunction "1_1") (pintype "passive"))
      (node (ref "L1") (pin "2") (pinfunction "2_2") (pintype "passive"))
      (node (ref "R1") (pin "1") (pinfunction "1_1") (pintype "passive"))
      (node (ref "R11") (pin "1") (pinfunction "1_1") (pintype "passive"))
      (node (ref "R3") (pin "2") (pinfunction "2_2") (pintype "passive"))
      (node (ref "TP2") (pin "1") (pinfunction "TP_1") (pintype "passive"))
    )
    (net (code "65") (name "Net-(TP7-TP)") (class "Default")
      (node (ref "J4") (pin "1") (pinfunction "1_1") (pintype "passive"))
      (node (ref "TP7") (pin "1") (pinfunction "TP_1") (pintype "passive"))
      (node (ref "U4") (pin "9") (pinfunction "ANT_9") (pintype "passive"))
    )
    (net (code "66") (name "Net-(U1-XIN)") (class "Default")
      (node (ref "C1") (pin "1") (pinfunction "1_1") (pintype "passive"))
      (node (ref "U1") (pin "20") (pinfunction "XIN_20") (pintype "input"))
      (node (ref "X1") (pin "1") (pinfunction "X1_1") (pintype "passive"))
    )
    (net (code "67") (name "Net-(U1-XOUT)") (class "Default")
      (node (ref "C14") (pin "2") (pinfunction "2_2") (pintype "passive"))
      (node (ref "U1") (pin "21") (pinfunction "XOUT_21") (pintype "output"))
      (node (ref "X1") (pin "3") (pinfunction "X2_3") (pintype "passive"))
    )
    (net (code "68") (name "Net-(U2-BST)") (class "Default")
      (node (ref "C8") (pin "2") (pinfunction "2_2") (pintype "passive"))
      (node (ref "U2") (pin "1") (pinfunction "BST_1") (pintype "passive"))
    )
    (net (code "69") (name "Net-(U2-COMP)") (class "Default")
      (node (ref "R12") (pin "1") (pinfunction "1_1") (pintype "passive"))
      (node (ref "U2") (pin "6") (pinfunction "COMP_6") (pintype "passive"))
    )
    (net (code "70") (name "Net-(U2-FB)") (class "Default")
      (node (ref "R11") (pin "2") (pinfunction "2_2") (pintype "passive"))
      (node (ref "R13") (pin "1") (pinfunction "1_1") (pintype "passive"))
      (node (ref "U2") (pin "5") (pinfunction "FB_5") (pintype "input"))
    )
    (net (code "71") (name "Net-(U2-SS)") (class "Default")
      (node (ref "C16") (pin "1") (pinfunction "1_1") (pintype "passive"))
      (node (ref "U2") (pin "4") (pinfunction "SS_4") (pintype "input"))
    )
    (net (code "72") (name "Net-(U2-SW)") (class "Default")
      (node (ref "L1") (pin "1") (pinfunction "1_1") (pintype "passive"))
      (node (ref "R10") (pin "2") (pinfunction "2_2") (pintype "passive"))
      (node (ref "U2") (pin "8") (pinfunction "SW_8") (pintype "passive"))
    )
    (net (code "73") (name "Net-(U3-OUT1)") (class "Default")
      (node (ref "P1") (pin "1") (pinfunction "1_1") (pintype "passive"))
      (node (ref "U3") (pin "6") (pinfunction "OUT1_6") (pintype "output"))
    )
    (net (code "74") (name "Net-(U3-OUT2)") (class "Default")
      (node (ref "P1") (pin "2") (pinfunction "2_2") (pintype "passive"))
      (node (ref "U3") (pin "8") (pinfunction "OUT2_8") (pintype "output"))
    )
    (net (code "75") (name "unconnected-(J2-ID-Pad4)") (class "Default")
      (node (ref "J2") (pin "4") (pinfunction "ID_4") (pintype "passive+no_connect"))
    )
    (net (code "76") (name "unconnected-(J2-VBUS-Pad1)") (class "Default")
      (node (ref "J2") (pin "1") (pinfunction "VBUS_1") (pintype "passive+no_connect"))
    )
    (net (code "77") (name "unconnected-(SW1-Pad2)") (class "Default")
      (node (ref "SW1") (pin "2") (pinfunction "2_2") (pintype "passive+no_connect"))
    )
    (net (code "78") (name "unconnected-(SW1-Pad3)") (class "Default")
      (node (ref "SW1") (pin "3") (pinfunction "3_3") (pintype "passive+no_connect"))
    )
    (net (code "79") (name "unconnected-(SW2-Pad2)") (class "Default")
      (node (ref "SW2") (pin "2") (pinfunction "2_2") (pintype "passive+no_connect"))
    )
    (net (code "80") (name "unconnected-(SW2-Pad3)") (class "Default")
      (node (ref "SW2") (pin "3") (pinfunction "3_3") (pintype "passive+no_connect"))
    )
  )
)
